# BMS_Switches.net
KiCad netlist of a schematic drawn in Altium Designer
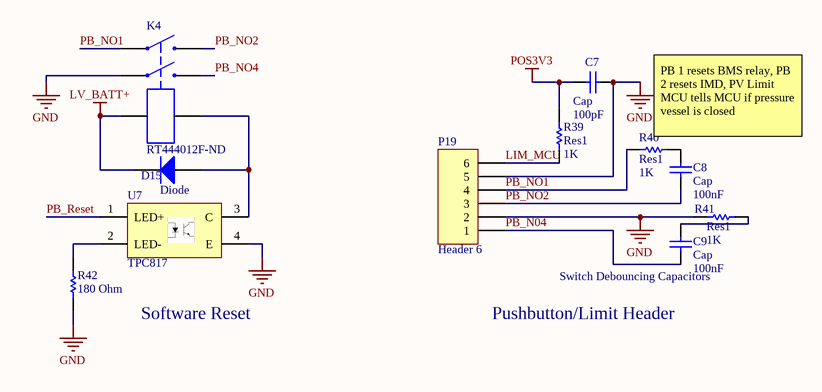
[diagram p0: BMS_Switches.SchDoc]

(export (version "E")
  (design (tool "Eeschema 10.0.6"))
  (components
    (comp (ref "C7")
      (value "Cap")
      (footprint "1206")
      (description "Capacitor")
      (fields (field (name "ALTIUM_VALUE") "100pF") (field (name "PUBLISHER") "Altium Limited"))
      (libsource (lib "Miscellaneous Devices") (part "Cap"))
    )
    (comp (ref "C8")
      (value "Cap")
      (footprint "1206")
      (description "Capacitor")
      (fields (field (name "ALTIUM_VALUE") "100nF") (field (name "PUBLISHER") "Altium Limited"))
      (libsource (lib "Miscellaneous Devices") (part "Cap"))
    )
    (comp (ref "C9")
      (value "Cap")
      (footprint "1206")
      (description "Capacitor")
      (fields (field (name "ALTIUM_VALUE") "100nF") (field (name "PUBLISHER") "Altium Limited"))
      (libsource (lib "Miscellaneous Devices") (part "Cap"))
    )
    (comp (ref "D15")
      (value "Diode")
      (footprint "1N4007")
      (description "Default Diode")
      (fields (field (name "PUBLISHER") "Altium Limited"))
      (libsource (lib "Miscellaneous Devices") (part "Diode"))
    )
    (comp (ref "K4")
      (value "RT444012F-ND")
      (footprint "RT444012F")
      (description "RELAY GEN PURPOSE DPST 8A 12V")
      (libsource (lib "ic") (part "RT444012F-ND"))
    )
    (comp (ref "P19")
      (value "Header 6")
      (footprint "6POS TERM BLOCK")
      (description "Header, 6-Pin")
      (fields (field (name "PUBLISHER") "Altium Limited"))
      (libsource (lib "Miscellaneous Connectors") (part "Header 6"))
    )
    (comp (ref "R39")
      (value "Res1")
      (footprint "1206")
      (description "Resistor")
      (fields (field (name "ALTIUM_VALUE") "1K") (field (name "PUBLISHER") "Altium Limited"))
      (libsource (lib "Miscellaneous Devices") (part "Res1"))
    )
    (comp (ref "R40")
      (value "Res1")
      (footprint "1206")
      (description "Resistor")
      (fields (field (name "ALTIUM_VALUE") "1K") (field (name "PUBLISHER") "Altium Limited"))
      (libsource (lib "Miscellaneous Devices") (part "Res1"))
    )
    (comp (ref "R41")
      (value "Res1")
      (footprint "1206")
      (description "Resistor")
      (fields (field (name "ALTIUM_VALUE") "1K") (field (name "PUBLISHER") "Altium Limited"))
      (libsource (lib "Miscellaneous Devices") (part "Res1"))
    )
    (comp (ref "R42")
      (value "180 Ohm")
      (footprint "1206")
      (description "Resistor")
      (fields (field (name "Comment") "Res1") (field (name "PUBLISHER") "Altium Limited"))
      (libsource (lib "Miscellaneous Devices") (part "Res1"))
    )
    (comp (ref "U7")
      (value "TPC817")
      (footprint "4-SOP")
      (description "Opto-Coupler")
      (libsource (lib "ic") (part "TPC817"))
    )
  )
  (nets
    (net (code "1") (name "/LIM_MCU") (class "Default")
      (node (ref "P19") (pin "6") (pinfunction "6_6") (pintype "passive"))
      (node (ref "R39") (pin "1") (pinfunction "1_1") (pintype "passive"))
    )
    (net (code "2") (name "/PB_N04") (class "Default")
      (node (ref "C9") (pin "1") (pinfunction "1_1") (pintype "passive"))
      (node (ref "P19") (pin "1") (pinfunction "1_1") (pintype "passive"))
    )
    (net (code "3") (name "/PB_NO1") (class "Default")
      (node (ref "K4") (pin "5") (pinfunction "5_5") (pintype "passive"))
      (node (ref "P19") (pin "4") (pinfunction "4_4") (pintype "passive"))
      (node (ref "R40") (pin "1") (pinfunction "1_1") (pintype "passive"))
    )
    (net (code "4") (name "/PB_NO2") (class "Default")
      (node (ref "C8") (pin "1") (pinfunction "1_1") (pintype "passive"))
      (node (ref "K4") (pin "6") (pinfunction "6_6") (pintype "passive"))
      (node (ref "P19") (pin "3") (pinfunction "3_3") (pintype "passive"))
    )
    (net (code "5") (name "/PB_NO4") (class "Default")
      (node (ref "K4") (pin "4") (pinfunction "4_4") (pintype "passive"))
    )
    (net (code "6") (name "/PB_Reset") (class "Default")
      (node (ref "U7") (pin "1") (pinfunction "LED+_1") (pintype "passive"))
    )
    (net (code "7") (name "GND") (class "Default")
      (node (ref "C7") (pin "1") (pinfunction "1_1") (pintype "passive"))
      (node (ref "K4") (pin "3") (pinfunction "3_3") (pintype "passive"))
      (node (ref "P19") (pin "2") (pinfunction "2_2") (pintype "passive"))
      (node (ref "P19") (pin "5") (pinfunction "5_5") (pintype "passive"))
      (node (ref "R41") (pin "1") (pinfunction "1_1") (pintype "passive"))
      (node (ref "R42") (pin "2") (pinfunction "2_2") (pintype "passive"))
      (node (ref "U7") (pin "4") (pinfunction "E_4") (pintype "passive"))
    )
    (net (code "8") (name "LV_BATT+") (class "Default")
      (node (ref "D15") (pin "2") (pinfunction "K_2") (pintype "passive"))
      (node (ref "K4") (pin "1") (pinfunction "1_1") (pintype "passive"))
    )
    (net (code "9") (name "Net-(C8-Pad2)") (class "Default")
      (node (ref "C8") (pin "2") (pinfunction "2_2") (pintype "passive"))
      (node (ref "R40") (pin "2") (pinfunction "2_2") (pintype "passive"))
    )
    (net (code "10") (name "Net-(C9-Pad2)") (class "Default")
      (node (ref "C9") (pin "2") (pinfunction "2_2") (pintype "passive"))
      (node (ref "R41") (pin "2") (pinfunction "2_2") (pintype "passive"))
    )
    (net (code "11") (name "Net-(D15-A)") (class "Default")
      (node (ref "D15") (pin "1") (pinfunction "A_1") (pintype "passive"))
      (node (ref "K4") (pin "2") (pinfunction "2_2") (pintype "passive"))
      (node (ref "U7") (pin "3") (pinfunction "C_3") (pintype "open_collector"))
    )
    (net (code "12") (name "Net-(U7-LED-)") (class "Default")
      (node (ref "R42") (pin "1") (pinfunction "1_1") (pintype "passive"))
      (node (ref "U7") (pin "2") (pinfunction "LED-_2") (pintype "open_emitter"))
    )
    (net (code "13") (name "POS3V3") (class "Default")
      (node (ref "C7") (pin "2") (pinfunction "2_2") (pintype "passive"))
      (node (ref "R39") (pin "2") (pinfunction "2_2") (pintype "passive"))
    )
  )
)
